# ColorSS_SCH.net
KiCad netlist of a schematic drawn in Altium Designer
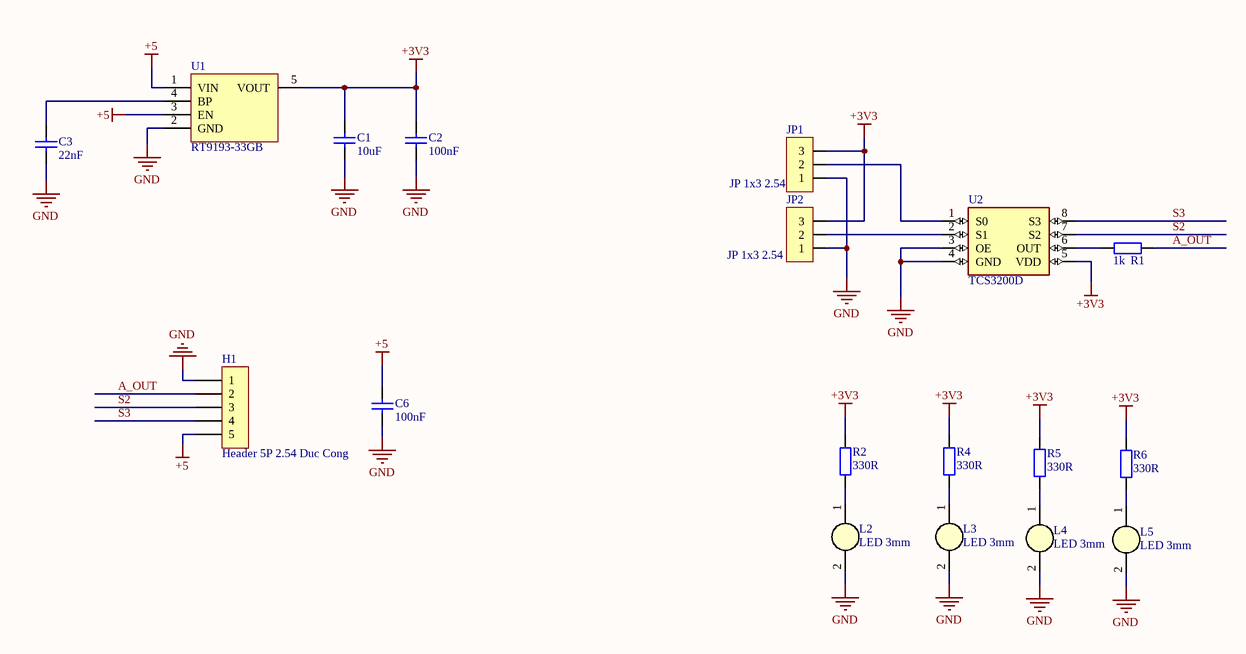
[diagram p0: ColorSS_SCH.SchDoc]

(export (version "E")
  (design (tool "Eeschema 10.0.6"))
  (components
    (comp (ref "C1")
      (value "10uF")
      (footprint "tu 0603")
      (description "Dán")
      (libsource (lib "namnt_Lib") (part "Tu 0603 106 16V 20%"))
    )
    (comp (ref "C2")
      (value "100nF")
      (footprint "tu 0603")
      (description "Dán")
      (libsource (lib "namnt_Lib") (part "Tu 0603 104 50V 10%"))
    )
    (comp (ref "C3")
      (value "22nF")
      (footprint "tu 0603")
      (description "Dán")
      (libsource (lib "namnt_Lib") (part "Tu 0603 104 50V 10%"))
    )
    (comp (ref "C6")
      (value "100nF")
      (footprint "tu 0603")
      (description "Dán")
      (libsource (lib "namnt_Lib") (part "Tu 0603 104 50V 10%"))
    )
    (comp (ref "H1")
      (value "Header 5P 2.54 Duc Cong")
      (footprint "Header 5P DC 2.54")
      (description "Cắm")
      (libsource (lib "namnt_Lib") (part "Header 5P 2.54 Duc Cong"))
    )
    (comp (ref "JP1")
      (value "JP 1x3 2.54")
      (footprint "JP 1x3 DT")
      (description "Cắm")
      (libsource (lib "namnt_Lib") (part "JP 1x3 2.54 Duc Thang"))
    )
    (comp (ref "JP2")
      (value "JP 1x3 2.54")
      (footprint "JP 1x3 DT")
      (description "Cắm")
      (libsource (lib "namnt_Lib") (part "JP 1x3 2.54 Duc Thang"))
    )
    (comp (ref "L2")
      (value "LED 3mm")
      (footprint "LED-3MM-WHITE")
      (description "Cắm")
      (libsource (lib "namnt_Lib") (part "LED 3mm Trang"))
    )
    (comp (ref "L3")
      (value "LED 3mm")
      (footprint "LED-3MM-WHITE")
      (description "Cắm")
      (libsource (lib "namnt_Lib") (part "LED 3mm Trang"))
    )
    (comp (ref "L4")
      (value "LED 3mm")
      (footprint "LED-3MM-WHITE")
      (description "Cắm")
      (libsource (lib "namnt_Lib") (part "LED 3mm Trang"))
    )
    (comp (ref "L5")
      (value "LED 3mm")
      (footprint "LED-3MM-WHITE")
      (description "Cắm")
      (libsource (lib "namnt_Lib") (part "LED 3mm Trang"))
    )
    (comp (ref "R1")
      (value "1k")
      (footprint "tro smd 0603")
      (description "Dán")
      (libsource (lib "namnt_Lib") (part "Tro 0603 1% 1k"))
    )
    (comp (ref "R2")
      (value "330R")
      (footprint "tro smd 0603")
      (description "Dán")
      (libsource (lib "namnt_Lib") (part "Tro 0603 5% 330R"))
    )
    (comp (ref "R4")
      (value "330R")
      (footprint "tro smd 0603")
      (description "Dán")
      (libsource (lib "namnt_Lib") (part "Tro 0603 5% 330R"))
    )
    (comp (ref "R5")
      (value "330R")
      (footprint "tro smd 0603")
      (description "Dán")
      (libsource (lib "namnt_Lib") (part "Tro 0603 5% 330R"))
    )
    (comp (ref "R6")
      (value "330R")
      (footprint "tro smd 0603")
      (description "Dán")
      (libsource (lib "namnt_Lib") (part "Tro 0603 5% 330R"))
    )
    (comp (ref "U1")
      (value "RT9193-33GB")
      (footprint "SOT23-5")
      (description "Linear Voltage Regulator IC 1 Output 300mA SOT-23-5")
      (fields (field (name "MANUFACTURER") "Richtek USA Inc."))
      (libsource (lib "namnt_Lib") (part "REG_5.5V-3.3V-0.3A-1W-SOT-23-5"))
    )
    (comp (ref "U2")
      (value "TCS3200D")
      (footprint "SOIC8")
      (description "Color Sensor - Auto Power Down 8-SOIC (0.154, 3.90mm Width)")
      (fields (field (name "MF") "ams"))
      (libsource (lib "namnt_Lib") (part "TCS3200D"))
    )
  )
  (nets
    (net (code "1") (name "+3V3") (class "Default")
      (node (ref "C1") (pin "1") (pinfunction "1_1") (pintype "passive"))
      (node (ref "C2") (pin "1") (pinfunction "1_1") (pintype "passive"))
      (node (ref "JP1") (pin "3") (pinfunction "3_3") (pintype "passive"))
      (node (ref "JP2") (pin "3") (pinfunction "3_3") (pintype "passive"))
      (node (ref "R2") (pin "2") (pinfunction "2_2") (pintype "passive"))
      (node (ref "R4") (pin "2") (pinfunction "2_2") (pintype "passive"))
      (node (ref "R5") (pin "2") (pinfunction "2_2") (pintype "passive"))
      (node (ref "R6") (pin "2") (pinfunction "2_2") (pintype "passive"))
      (node (ref "U1") (pin "5") (pinfunction "VOUT_5") (pintype "passive"))
      (node (ref "U2") (pin "5") (pinfunction "VDD_5") (pintype "bidirectional"))
    )
    (net (code "2") (name "+5") (class "Default")
      (node (ref "C6") (pin "1") (pinfunction "1_1") (pintype "passive"))
      (node (ref "H1") (pin "5") (pinfunction "5_5") (pintype "passive"))
      (node (ref "U1") (pin "1") (pinfunction "VIN_1") (pintype "passive"))
      (node (ref "U1") (pin "3") (pinfunction "EN_3") (pintype "passive"))
    )
    (net (code "3") (name "/A_OUT") (class "Default")
      (node (ref "H1") (pin "2") (pinfunction "2_2") (pintype "passive"))
      (node (ref "R1") (pin "2") (pinfunction "2_2") (pintype "passive"))
    )
    (net (code "4") (name "/S2") (class "Default")
      (node (ref "H1") (pin "3") (pinfunction "3_3") (pintype "passive"))
      (node (ref "U2") (pin "7") (pinfunction "S2_7") (pintype "bidirectional"))
    )
    (net (code "5") (name "/S3") (class "Default")
      (node (ref "H1") (pin "4") (pinfunction "4_4") (pintype "passive"))
      (node (ref "U2") (pin "8") (pinfunction "S3_8") (pintype "bidirectional"))
    )
    (net (code "6") (name "GND") (class "Default")
      (node (ref "C1") (pin "2") (pinfunction "2_2") (pintype "passive"))
      (node (ref "C2") (pin "2") (pinfunction "2_2") (pintype "passive"))
      (node (ref "C3") (pin "2") (pinfunction "2_2") (pintype "passive"))
      (node (ref "C6") (pin "2") (pinfunction "2_2") (pintype "passive"))
      (node (ref "H1") (pin "1") (pinfunction "1_1") (pintype "passive"))
      (node (ref "JP1") (pin "1") (pinfunction "1_1") (pintype "passive"))
      (node (ref "JP2") (pin "1") (pinfunction "1_1") (pintype "passive"))
      (node (ref "L2") (pin "2") (pinfunction "K_2") (pintype "passive"))
      (node (ref "L3") (pin "2") (pinfunction "K_2") (pintype "passive"))
      (node (ref "L4") (pin "2") (pinfunction "K_2") (pintype "passive"))
      (node (ref "L5") (pin "2") (pinfunction "K_2") (pintype "passive"))
      (node (ref "U1") (pin "2") (pinfunction "GND_2") (pintype "passive"))
      (node (ref "U2") (pin "3") (pinfunction "OE_3") (pintype "bidirectional"))
      (node (ref "U2") (pin "4") (pinfunction "GND_4") (pintype "bidirectional"))
    )
    (net (code "7") (name "Net-(L2-A)") (class "Default")
      (node (ref "L2") (pin "1") (pinfunction "A_1") (pintype "passive"))
      (node (ref "R2") (pin "1") (pinfunction "1_1") (pintype "passive"))
    )
    (net (code "8") (name "Net-(L3-A)") (class "Default")
      (node (ref "L3") (pin "1") (pinfunction "A_1") (pintype "passive"))
      (node (ref "R4") (pin "1") (pinfunction "1_1") (pintype "passive"))
    )
    (net (code "9") (name "Net-(L4-A)") (class "Default")
      (node (ref "L4") (pin "1") (pinfunction "A_1") (pintype "passive"))
      (node (ref "R5") (pin "1") (pinfunction "1_1") (pintype "passive"))
    )
    (net (code "10") (name "Net-(L5-A)") (class "Default")
      (node (ref "L5") (pin "1") (pinfunction "A_1") (pintype "passive"))
      (node (ref "R6") (pin "1") (pinfunction "1_1") (pintype "passive"))
    )
    (net (code "11") (name "Net-(U1-BP)") (class "Default")
      (node (ref "C3") (pin "1") (pinfunction "1_1") (pintype "passive"))
      (node (ref "U1") (pin "4") (pinfunction "BP_4") (pintype "passive"))
    )
    (net (code "12") (name "Net-(U2-OUT)") (class "Default")
      (node (ref "R1") (pin "1") (pinfunction "1_1") (pintype "passive"))
      (node (ref "U2") (pin "6") (pinfunction "OUT_6") (pintype "bidirectional"))
    )
    (net (code "13") (name "Net-(U2-S0)") (class "Default")
      (node (ref "JP1") (pin "2") (pinfunction "2_2") (pintype "passive"))
      (node (ref "U2") (pin "1") (pinfunction "S0_1") (pintype "bidirectional"))
    )
    (net (code "14") (name "Net-(U2-S1)") (class "Default")
      (node (ref "JP2") (pin "2") (pinfunction "2_2") (pintype "passive"))
      (node (ref "U2") (pin "2") (pinfunction "S1_2") (pintype "bidirectional"))
    )
  )
)
